# Power.net
KiCad netlist of a schematic drawn in Altium Designer
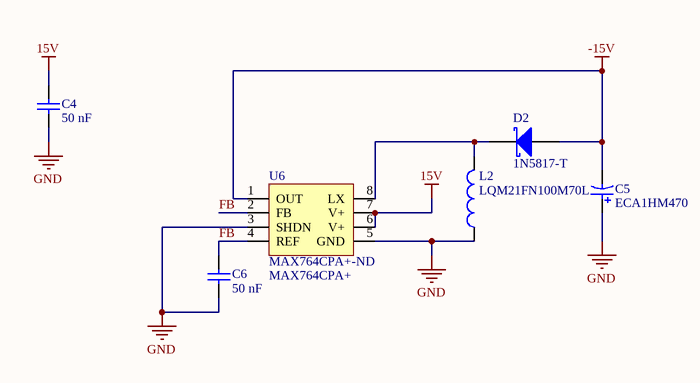
[diagram p0: Power.SchDoc]

(export (version "E")
  (design (tool "Eeschema 10.0.6"))
  (components
    (comp (ref "C4")
      (value "50 nF")
      (footprint "CAPC0805(2012)75_M")
      (description "CAP 0.5pF 50V ±0.1pF 0805 (2012 Metric) Thickness 0.75mm SMD")
      (fields (field (name "TOLERANCE") "Â±0.1pF"))
      (libsource (lib "Altium Content Vault") (part "CMP-1036-00018-1"))
    )
    (comp (ref "C5")
      (value "ECA1HM470")
      (footprint "CAPPR55-250-1120X630X1220")
      (description "Aluminum Electrolytic Capacitor, 47 uF, +/- 20%, 50 V, -40 to 85 degC, 2-Pin THD, RoHS, Bulk")
      (fields (field (name "MANUFACTURER") "Panasonic") (field (name "TOLERANCE") "20%"))
      (libsource (lib "Altium Content Vault") (part "CMP-2100-03626-1"))
    )
    (comp (ref "C6")
      (value "50 nF")
      (footprint "CAPC0805(2012)75_M")
      (description "CAP 0.5pF 50V ±0.1pF 0805 (2012 Metric) Thickness 0.75mm SMD")
      (fields (field (name "TOLERANCE") "Â±0.1pF"))
      (libsource (lib "Altium Content Vault") (part "CMP-1036-00018-1"))
    )
    (comp (ref "D2")
      (value "1N5817-T")
      (footprint "DIOD-DO-41-P-2")
      (description "Schottky Barrier Rectifier, 1 A, 20 V, -65 to 125 degC, 2-Pin DO-41, RoHS, Tape and Reel")
      (fields (field (name "MANUFACTURER") "DiodesIncorporated"))
      (libsource (lib "Altium Content Vault") (part "DSKY-AK-2"))
    )
    (comp (ref "L2")
      (value "LQM21FN100M70L")
      (footprint "MURA-IND0805_L")
      (description "Fixed Inductor, 10 uH, +/-20%, -55 to 125 degC, 2-Pin SMD (0805), RoHS, Tape and Reel")
      (fields (field (name "MANUFACTURER") "Murata"))
      (libsource (lib "Altium Content Vault") (part "IND-2"))
    )
    (comp (ref "U6")
      (value "MAX764CPA+-ND")
      (footprint "PDIP300-P8")
      (description "IC REG BUCK BST INV ADJ/-5V 8DIP")
      (fields (field (name "MANUFACTURER PN") "MAX764CPA+"))
      (libsource (lib "Boost_lib") (part "MAX764CPA+-ND"))
    )
  )
  (nets
    (net (code "1") (name "-15V") (class "Default")
      (node (ref "C5") (pin "2") (pinfunction "2_2") (pintype "passive"))
      (node (ref "D2") (pin "1") (pinfunction "A_1") (pintype "passive"))
      (node (ref "U6") (pin "1") (pinfunction "OUT_1") (pintype "passive"))
    )
    (net (code "2") (name "/FB") (class "Default")
      (node (ref "C6") (pin "1") (pinfunction "1_1") (pintype "passive"))
      (node (ref "U6") (pin "2") (pinfunction "FB_2") (pintype "passive"))
      (node (ref "U6") (pin "4") (pinfunction "REF_4") (pintype "passive"))
    )
    (net (code "3") (name "15V") (class "Default")
      (node (ref "C4") (pin "1") (pinfunction "1_1") (pintype "passive"))
      (node (ref "U6") (pin "6") (pinfunction "V+_6") (pintype "passive"))
      (node (ref "U6") (pin "7") (pinfunction "V+_7") (pintype "passive"))
    )
    (net (code "4") (name "GND") (class "Default")
      (node (ref "C4") (pin "2") (pinfunction "2_2") (pintype "passive"))
      (node (ref "C5") (pin "1") (pinfunction "1_1") (pintype "passive"))
      (node (ref "C6") (pin "2") (pinfunction "2_2") (pintype "passive"))
      (node (ref "L2") (pin "1") (pinfunction "1_1") (pintype "passive"))
      (node (ref "U6") (pin "3") (pinfunction "SHDN_3") (pintype "passive"))
      (node (ref "U6") (pin "5") (pinfunction "GND_5") (pintype "passive"))
    )
    (net (code "5") (name "Net-(D2-K)") (class "Default")
      (node (ref "D2") (pin "2") (pinfunction "K_2") (pintype "passive"))
      (node (ref "L2") (pin "2") (pinfunction "2_2") (pintype "passive"))
      (node (ref "U6") (pin "8") (pinfunction "LX_8") (pintype "passive"))
    )
  )
)
